# 7_dc_dc_3v3_eps_beacon.net
KiCad netlist of a schematic drawn in Altium Designer
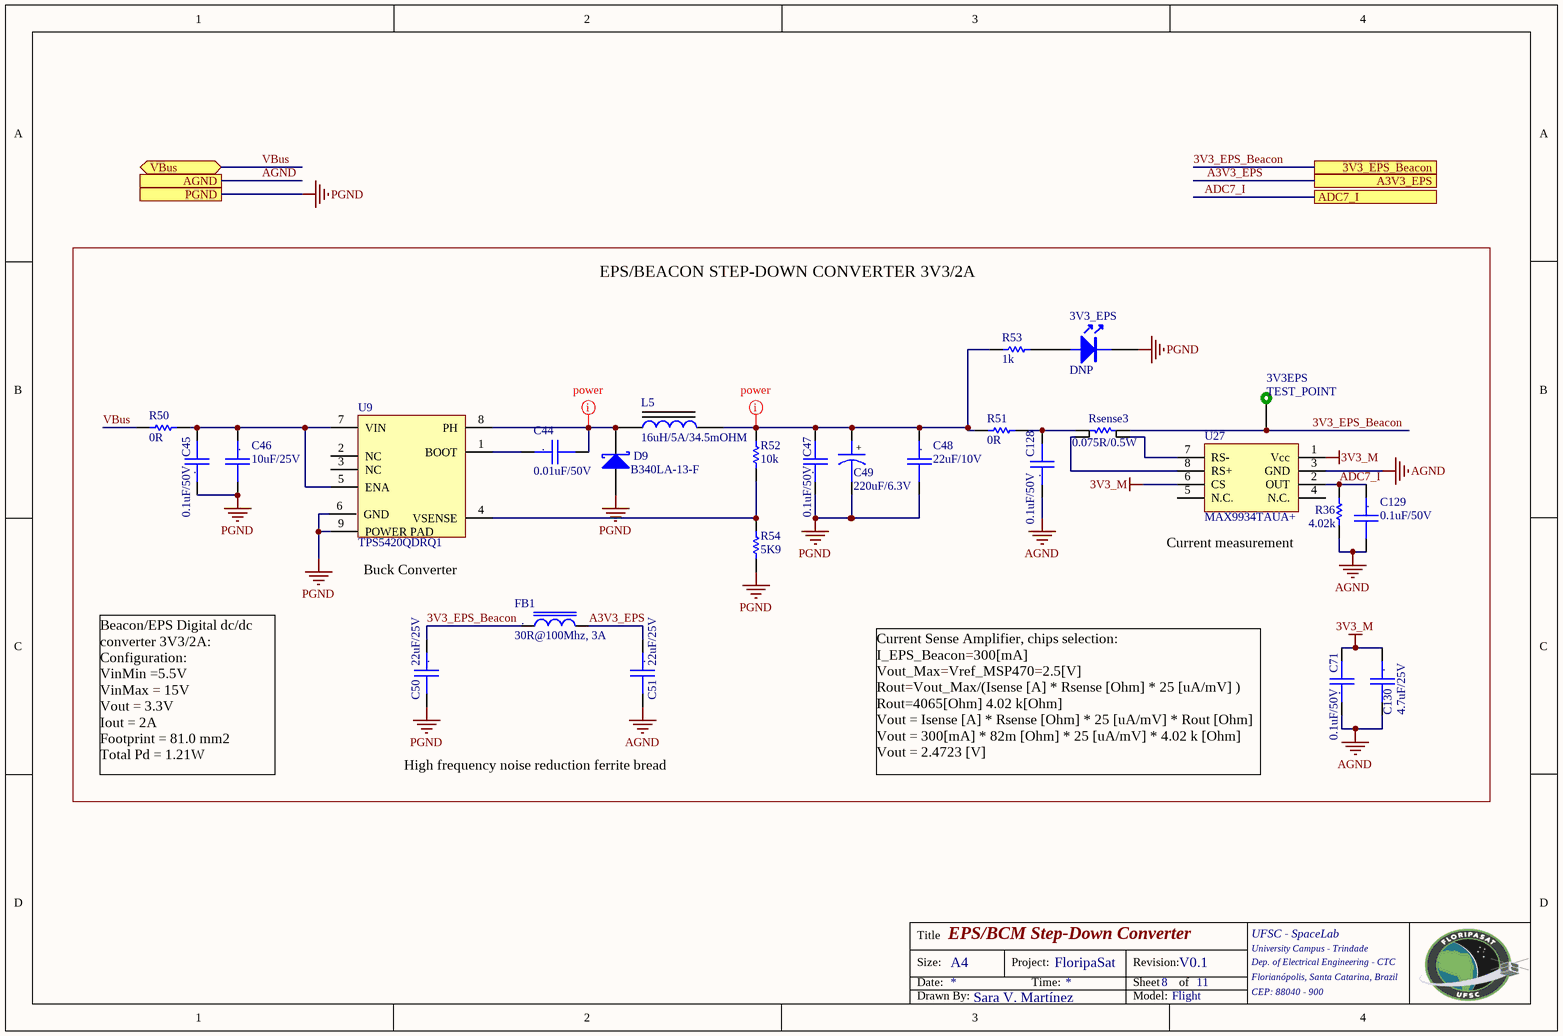
[diagram p0: 7_dc_dc_3v3_eps_beacon.schdoc]

(export (version "E")
  (design (tool "Eeschema 10.0.6"))
  (components
    (comp (ref "3V3EPS")
      (value "TEST_POINT")
      (footprint "TEST_POINT")
      (description "Test point")
      (libsource (lib "PCB_Project_FlightModel_EPS") (part "TEST_POINT"))
    )
    (comp (ref "3V3_EPS")
      (value "DNP")
      (footprint "0603-LED")
      (description "SMD Green LED")
      (fields (field (name "PARTNUMBER") "150060VS75000") (field (name "MANUFACTURER") "Wurth Electronics"))
      (libsource (lib "PCB_Project_FlightModel_EPS") (part "LED/G_0603"))
    )
    (comp (ref "C44")
      (value "0.01uF/50V")
      (footprint "CC0805")
      (description "CAP CER 0.01uF 50V 10% X7R 0805")
      (fields (field (name "PARTNUMBER") "08055C103KAT4A") (field (name "MANUFACTURER") "Kyocera AVX"))
      (libsource (lib "PCB_Project_FlightModel_EPS") (part "Cap_Cer_X7R_0.01uF_50V_0805"))
    )
    (comp (ref "C45")
      (value "0.1uF/50V")
      (footprint "CC0805")
      (description "CAP CER 0.1UF 50V 10% X7R 0805")
      (fields (field (name "PARTNUMBER") "CC0805KRX7R9BB104") (field (name "MANUFACTURER") "Yageo"))
      (libsource (lib "PCB_Project_FlightModel_EPS") (part "Cap_Cer_X7R_0.1uF_50V_0805"))
    )
    (comp (ref "C46")
      (value "10uF/25V")
      (footprint "CC1206")
      (description "CAP CER 10uF 25V 10% X7R 1206")
      (fields (field (name "PARTNUMBER") "GRM31CR71E106KA12L") (field (name "MANUFACTURER") "Murata"))
      (libsource (lib "PCB_Project_FlightModel_EPS") (part "Cap_Cer_X7R_10uF_25V_1206"))
    )
    (comp (ref "C47")
      (value "0.1uF/50V")
      (footprint "CC0805")
      (description "CAP CER 0.1UF 50V 10% X7R 0805")
      (fields (field (name "PARTNUMBER") "CC0805KRX7R9BB104") (field (name "MANUFACTURER") "Yageo"))
      (libsource (lib "PCB_Project_FlightModel_EPS") (part "Cap_Cer_X7R_0.1uF_50V_0805"))
    )
    (comp (ref "C48")
      (value "22uF/10V")
      (footprint "CC1206")
      (description "CAP CER 22uF 10V 10% X7R 1206")
      (fields (field (name "PARTNUMBER") "GRM31CR71A226KE15L") (field (name "MANUFACTURER") "Murata"))
      (libsource (lib "PCB_Project_FlightModel_EPS") (part "Cap_Cer_X7R_22uF_10V_1206"))
    )
    (comp (ref "C49")
      (value "220uF/6.3V")
      (footprint "FloripaSatPcbLib:cc1210")
      (description "CAP Tantalum 220uF 6.3V 20% 1210")
      (fields (field (name "PARTNUMBER") "6TPE220MAZB") (field (name "MANUFACTURER") "Panasonic"))
      (libsource (lib "PCB_Project_FlightModel_EPS") (part "Cap_Tant_SMD_220uF_6.3V_1210"))
    )
    (comp (ref "C50")
      (value "22uF/25V")
      (footprint "CC1210")
      (description "CAP CER 22uF 25V 10% X7R 1210")
      (fields (field (name "PARTNUMBER") "GRM32ER71E226KE15L") (field (name "MANUFACTURER") "Murata"))
      (libsource (lib "PCB_Project_FlightModel_EPS") (part "Cap_Cer_X7R_22uF_25V_1210"))
    )
    (comp (ref "C51")
      (value "22uF/25V")
      (footprint "CC1210")
      (description "CAP CER 22uF 25V 10% X7R 1210")
      (fields (field (name "PARTNUMBER") "GRM32ER71E226KE15L") (field (name "MANUFACTURER") "Murata"))
      (libsource (lib "PCB_Project_FlightModel_EPS") (part "Cap_Cer_X7R_22uF_25V_1210"))
    )
    (comp (ref "C71")
      (value "0.1uF/50V")
      (footprint "CC0603")
      (description "CAP CER 0.1UF 50V 10% X7R 0603")
      (fields (field (name "PARTNUMBER") "CC0603KPX7R9BB104") (field (name "MANUFACTURER") "Yageo"))
      (libsource (lib "PCB_Project_FlightModel_EPS") (part "Cap_Cer_X7R_0.1uF_50V_0603"))
    )
    (comp (ref "C128")
      (value "0.1uF/50V")
      (footprint "CC0603")
      (description "CAP CER 0.1UF 50V 10% X7R 0603")
      (fields (field (name "PARTNUMBER") "CC0603KPX7R9BB104") (field (name "MANUFACTURER") "Yageo"))
      (libsource (lib "PCB_Project_FlightModel_EPS") (part "Cap_Cer_X7R_0.1uF_50V_0603"))
    )
    (comp (ref "C129")
      (value "0.1uF/50V")
      (footprint "CC0603")
      (description "CAP CER 0.1UF 50V 10% X7R 0603")
      (fields (field (name "PARTNUMBER") "CC0603KPX7R9BB104") (field (name "MANUFACTURER") "Yageo"))
      (libsource (lib "PCB_Project_FlightModel_EPS") (part "Cap_Cer_X7R_0.1uF_50V_0603"))
    )
    (comp (ref "C130")
      (value "4.7uF/25V")
      (footprint "CC0805")
      (description "CAP CER 4.7uF 25V 10% X7R 0805")
      (fields (field (name "PARTNUMBER") "CC0805KKX7R8BB475") (field (name "MANUFACTURER") "Yageo"))
      (libsource (lib "PCB_Project_FlightModel_EPS") (part "Cap_Cer_X7R_4.7uF_25V_0805"))
    )
    (comp (ref "D9")
      (value "B340LA-13-F")
      (footprint "DO-214AC")
      (description "DIODE SCHOTTKY 40V 3A B340LA-13-F")
      (fields (field (name "MANUFACTURER") "Diodes"))
      (libsource (lib "PCB_Project_FlightModel_EPS") (part "DIODE_SCHOTTKY_40V_3A_B340LA-13-F"))
    )
    (comp (ref "FB1")
      (value "30R@100Mhz, 3A")
      (footprint "IND0805")
      (description "Ferrite Bead 30 OHM 3A 100MHz")
      (fields (field (name "PARTNUMBER") "BLM21PG300SN1D") (field (name "MANUFACTURER") "Murata"))
      (libsource (lib "PCB_Project_FlightModel_EPS") (part "FB_30R_3A_100MHz_0805"))
    )
    (comp (ref "L5")
      (value "16uH/5A/34.5mOHM")
      (footprint "IND_744325xxx")
      (description "INDUCTOR 16UH 5A SMD")
      (fields (field (name "PARTNUMBER") "7443251600") (field (name "MANUFACTURER") "Wurth Electronics"))
      (libsource (lib "PCB_Project_FlightModel_EPS") (part "IND_POWER_16uH_5A_35.5mR"))
    )
    (comp (ref "R36")
      (value "4.02k")
      (footprint "0805")
      (description "RES 4.02k OHM 1/8W 0.1% 0805")
      (fields (field (name "PARTNUMBER") "ERA-6AEB4021V") (field (name "MANUFACTURER") "Panasonic"))
      (libsource (lib "PCB_Project_FlightModel_EPS") (part "R4.02k_0.1%_1/8W_0805"))
    )
    (comp (ref "R50")
      (value "0R")
      (footprint "1206")
      (description "RES 0.0 OHM 3/4W JUMP 1206")
      (fields
        (field (name "PARTNUMBER") "HCJ1206ZT0R00")
        (field (name "MANUFACTURER") "Stackpole Electronics")
      )
      (libsource (lib "PCB_Project_FlightModel_EPS") (part "R0R_JUMPER_3/4W_1206"))
    )
    (comp (ref "R51")
      (value "0R")
      (footprint "1206")
      (description "RES 0.0 OHM 3/4W JUMP 1206")
      (fields
        (field (name "PARTNUMBER") "HCJ1206ZT0R00")
        (field (name "MANUFACTURER") "Stackpole Electronics")
      )
      (libsource (lib "PCB_Project_FlightModel_EPS") (part "R0R_JUMPER_3/4W_1206"))
    )
    (comp (ref "R52")
      (value "10k")
      (footprint "0805")
      (description "RES 10K OHM 1/8W 1%  0805")
      (fields (field (name "PARTNUMBER") "CRCW080510K0FKEA") (field (name "MANUFACTURER") "Vishay"))
      (libsource (lib "PCB_Project_FlightModel_EPS") (part "R10k_1%_1/8W_0805"))
    )
    (comp (ref "R53")
      (value "1k")
      (footprint "0603")
      (description "RES 1.0K OHM 1/8W 1% 0603")
      (fields (field (name "PARTNUMBER") "MCT06030C1001FP500") (field (name "MANUFACTURER") "Vishay"))
      (libsource (lib "PCB_Project_FlightModel_EPS") (part "R1.0k_1%_1/8W_0603"))
    )
    (comp (ref "R54")
      (value "5K9")
      (footprint "0805")
      (description "RES 5K9 OHM 1/8W 1% 0805")
      (fields (field (name "PARTNUMBER") "71-CRCW0805-5.9K-E3") (field (name "MANUFACTURER") "Vishay"))
      (libsource (lib "PCB_Project_FlightModel_EPS") (part "R5.9K_1%_1/8W_0805"))
    )
    (comp (ref "Rsense3")
      (value "0.075R/0.5W")
      (footprint "1206 - ohmite")
      (description "Current Sense Resistors - SMD 1/2W 0.075 OHMS 1% 4 Terminal")
      (fields (field (name "PARTNUMBER") "LVK12R075FER") (field (name "MANUFACTURER") "Ohmite"))
      (libsource (lib "PCB_Project_FlightModel_EPS") (part "R0.075R_1%_0.5W_1206"))
    )
    (comp (ref "U9")
      (value "TPS5420QDRQ1")
      (footprint "SO8 Power PAD")
      (fields (field (name "MANUFACTURER") "Texas Instruments"))
      (libsource (lib "PCB_Project_FlightModel_EPS") (part "TPS5420QDRQ1"))
    )
    (comp (ref "U27")
      (value "MAX9934TAUA+")
      (footprint "MSOP-8")
      (fields (field (name "MANUFACTURER") "Maxim"))
      (libsource (lib "PCB_Project_FlightModel_EPS") (part "MAX9934TAUA+"))
    )
  )
  (nets
    (net (code "1") (name "/3V3_EPS_Beacon") (class "Default")
      (node (ref "3V3EPS") (pin "1") (pinfunction "1_1") (pintype "passive"))
      (node (ref "C50") (pin "1") (pinfunction "1_1") (pintype "passive"))
      (node (ref "FB1") (pin "1") (pinfunction "1_1") (pintype "passive"))
      (node (ref "Rsense3") (pin "2") (pinfunction "2_2") (pintype "passive"))
    )
    (net (code "2") (name "/A3V3_EPS") (class "Default")
      (node (ref "C51") (pin "1") (pinfunction "1_1") (pintype "passive"))
      (node (ref "FB1") (pin "2") (pinfunction "2_2") (pintype "passive"))
    )
    (net (code "3") (name "/ADC7_I") (class "Default")
      (node (ref "C129") (pin "1") (pinfunction "1_1") (pintype "passive"))
      (node (ref "R36") (pin "2") (pinfunction "2_2") (pintype "passive"))
      (node (ref "U27") (pin "2") (pinfunction "OUT_2") (pintype "passive"))
    )
    (net (code "4") (name "/VBus") (class "Default")
      (node (ref "R50") (pin "2") (pinfunction "2_2") (pintype "passive"))
    )
    (net (code "5") (name "3V3_M") (class "Default")
      (node (ref "C130") (pin "1") (pinfunction "1_1") (pintype "passive"))
      (node (ref "C71") (pin "2") (pinfunction "2_2") (pintype "passive"))
      (node (ref "U27") (pin "1") (pinfunction "Vcc_1") (pintype "passive"))
      (node (ref "U27") (pin "6") (pinfunction "CS_6") (pintype "passive"))
    )
    (net (code "6") (name "AGND") (class "Default")
      (node (ref "C128") (pin "1") (pinfunction "1_1") (pintype "passive"))
      (node (ref "C129") (pin "2") (pinfunction "2_2") (pintype "passive"))
      (node (ref "C130") (pin "2") (pinfunction "2_2") (pintype "passive"))
      (node (ref "C51") (pin "2") (pinfunction "2_2") (pintype "passive"))
      (node (ref "C71") (pin "1") (pinfunction "1_1") (pintype "passive"))
      (node (ref "R36") (pin "1") (pinfunction "1_1") (pintype "passive"))
      (node (ref "U27") (pin "3") (pinfunction "GND_3") (pintype "passive"))
    )
    (net (code "7") (name "Net-(3V3_EPS-A)") (class "Default")
      (node (ref "3V3_EPS") (pin "1") (pinfunction "A_1") (pintype "passive"))
      (node (ref "R53") (pin "1") (pinfunction "1_1") (pintype "passive"))
    )
    (net (code "8") (name "Net-(C47-Pad2)") (class "Default")
      (node (ref "C47") (pin "2") (pinfunction "2_2") (pintype "passive"))
      (node (ref "C48") (pin "1") (pinfunction "1_1") (pintype "passive"))
      (node (ref "C49") (pin "1") (pinfunction "1_1") (pintype "passive"))
      (node (ref "L5") (pin "2") (pinfunction "2_2") (pintype "passive"))
      (node (ref "R51") (pin "2") (pinfunction "2_2") (pintype "passive"))
      (node (ref "R52") (pin "2") (pinfunction "2_2") (pintype "passive"))
      (node (ref "R53") (pin "2") (pinfunction "2_2") (pintype "passive"))
    )
    (net (code "9") (name "Net-(C128-Pad2)") (class "Default")
      (node (ref "C128") (pin "2") (pinfunction "2_2") (pintype "passive"))
      (node (ref "R51") (pin "1") (pinfunction "1_1") (pintype "passive"))
      (node (ref "Rsense3") (pin "1") (pinfunction "1_1") (pintype "passive"))
    )
    (net (code "10") (name "Net-(D9-K)") (class "Default")
      (node (ref "C44") (pin "2") (pinfunction "2_2") (pintype "passive"))
      (node (ref "D9") (pin "1") (pinfunction "K_1") (pintype "passive"))
      (node (ref "L5") (pin "1") (pinfunction "1_1") (pintype "passive"))
      (node (ref "U9") (pin "8") (pinfunction "PH_8") (pintype "passive"))
    )
    (net (code "11") (name "Net-(U9-BOOT)") (class "Default")
      (node (ref "C44") (pin "1") (pinfunction "1_1") (pintype "passive"))
      (node (ref "U9") (pin "1") (pinfunction "BOOT_1") (pintype "passive"))
    )
    (net (code "12") (name "Net-(U9-ENA)") (class "Default")
      (node (ref "C45") (pin "2") (pinfunction "2_2") (pintype "passive"))
      (node (ref "C46") (pin "1") (pinfunction "1_1") (pintype "passive"))
      (node (ref "R50") (pin "1") (pinfunction "1_1") (pintype "passive"))
      (node (ref "U9") (pin "5") (pinfunction "ENA_5") (pintype "passive"))
      (node (ref "U9") (pin "7") (pinfunction "VIN_7") (pintype "passive"))
    )
    (net (code "13") (name "Net-(U9-VSENSE)") (class "Default")
      (node (ref "R52") (pin "1") (pinfunction "1_1") (pintype "passive"))
      (node (ref "R54") (pin "2") (pinfunction "2_2") (pintype "passive"))
      (node (ref "U9") (pin "4") (pinfunction "VSENSE_4") (pintype "passive"))
    )
    (net (code "14") (name "Net-(U27-RS+)") (class "Default")
      (node (ref "Rsense3") (pin "3") (pinfunction "3_3") (pintype "passive"))
      (node (ref "U27") (pin "8") (pinfunction "RS+_8") (pintype "passive"))
    )
    (net (code "15") (name "Net-(U27-RS-)") (class "Default")
      (node (ref "Rsense3") (pin "4") (pinfunction "4_4") (pintype "passive"))
      (node (ref "U27") (pin "7") (pinfunction "RS-_7") (pintype "passive"))
    )
    (net (code "16") (name "PGND") (class "Default")
      (node (ref "3V3_EPS") (pin "2") (pinfunction "K_2") (pintype "passive"))
      (node (ref "C45") (pin "1") (pinfunction "1_1") (pintype "passive"))
      (node (ref "C46") (pin "2") (pinfunction "2_2") (pintype "passive"))
      (node (ref "C47") (pin "1") (pinfunction "1_1") (pintype "passive"))
      (node (ref "C48") (pin "2") (pinfunction "2_2") (pintype "passive"))
      (node (ref "C49") (pin "2") (pinfunction "2_2") (pintype "passive"))
      (node (ref "C50") (pin "2") (pinfunction "2_2") (pintype "passive"))
      (node (ref "D9") (pin "2") (pinfunction "A_2") (pintype "passive"))
      (node (ref "R54") (pin "1") (pinfunction "1_1") (pintype "passive"))
      (node (ref "U9") (pin "6") (pinfunction "GND_6") (pintype "passive"))
      (node (ref "U9") (pin "9") (pinfunction "POWER_PAD_9") (pintype "passive"))
    )
    (net (code "17") (name "unconnected-(U9-NC-Pad2)") (class "Default")
      (node (ref "U9") (pin "2") (pinfunction "NC_2") (pintype "passive"))
    )
    (net (code "18") (name "unconnected-(U9-NC-Pad3)") (class "Default")
      (node (ref "U9") (pin "3") (pinfunction "NC_3") (pintype "passive"))
    )
    (net (code "19") (name "unconnected-(U27-N.C.-Pad4)") (class "Default")
      (node (ref "U27") (pin "4") (pinfunction "N.C._4") (pintype "passive"))
    )
    (net (code "20") (name "unconnected-(U27-N.C.-Pad5)") (class "Default")
      (node (ref "U27") (pin "5") (pinfunction "N.C._5") (pintype "passive"))
    )
  )
)
